# PMTF_Middle_board.net
KiCad netlist of a schematic drawn in Altium Designer
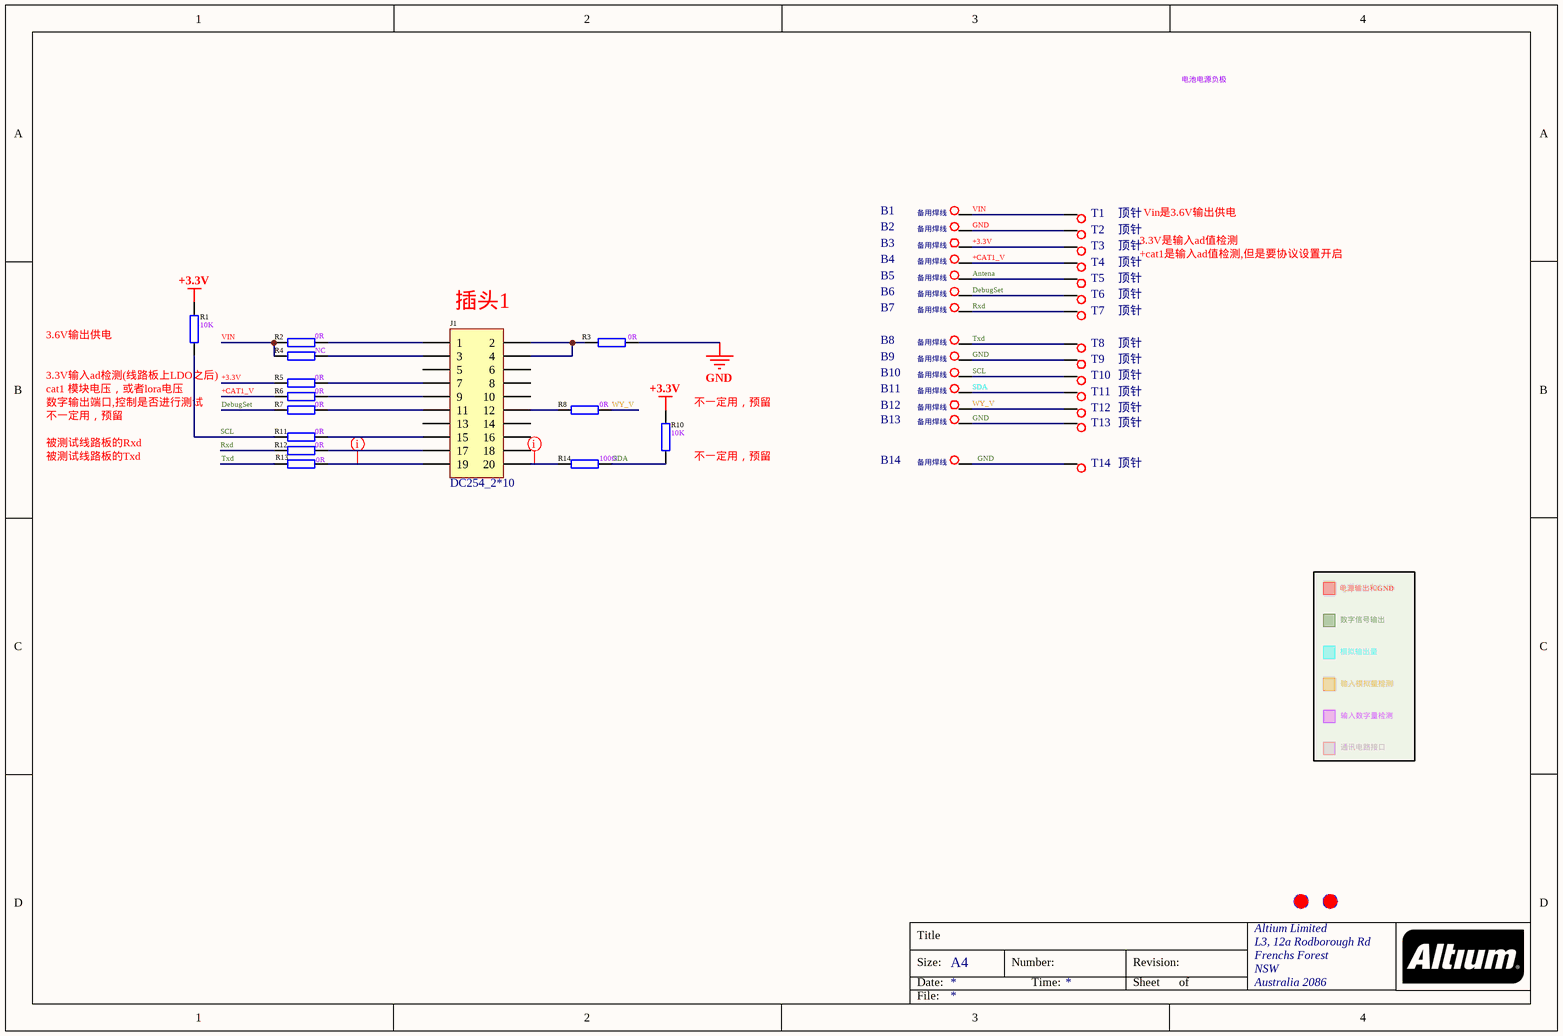
[diagram p0: PMTF_Middle_board.schdoc]

(export (version "E")
  (design (tool "Eeschema 10.0.6"))
  (components
    (comp (ref "B1")
      (value "备用焊线")
      (footprint "Connector:TestPoint")
      (description "通孔测试点")
      (fields (field (name "PART NUMBER") "AD_WXHJ_TEST-POINT_01"))
      (libsource (lib "Database_Libs2") (part "TEST-POINT"))
    )
    (comp (ref "B2")
      (value "备用焊线")
      (footprint "Connector:TestPoint")
      (description "通孔测试点")
      (fields (field (name "PART NUMBER") "AD_WXHJ_TEST-POINT_01"))
      (libsource (lib "Database_Libs2") (part "TEST-POINT"))
    )
    (comp (ref "B3")
      (value "备用焊线")
      (footprint "Connector:TestPoint")
      (description "通孔测试点")
      (fields (field (name "PART NUMBER") "AD_WXHJ_TEST-POINT_01"))
      (libsource (lib "Database_Libs2") (part "TEST-POINT"))
    )
    (comp (ref "B4")
      (value "备用焊线")
      (footprint "Connector:TestPoint")
      (description "通孔测试点")
      (fields (field (name "PART NUMBER") "AD_WXHJ_TEST-POINT_01"))
      (libsource (lib "Database_Libs2") (part "TEST-POINT"))
    )
    (comp (ref "B5")
      (value "备用焊线")
      (footprint "Connector:TestPoint")
      (description "通孔测试点")
      (fields (field (name "PART NUMBER") "AD_WXHJ_TEST-POINT_01"))
      (libsource (lib "Database_Libs2") (part "TEST-POINT"))
    )
    (comp (ref "B6")
      (value "备用焊线")
      (footprint "Connector:TestPoint")
      (description "通孔测试点")
      (fields (field (name "PART NUMBER") "AD_WXHJ_TEST-POINT_01"))
      (libsource (lib "Database_Libs2") (part "TEST-POINT"))
    )
    (comp (ref "B7")
      (value "备用焊线")
      (footprint "Connector:TestPoint")
      (description "通孔测试点")
      (fields (field (name "PART NUMBER") "AD_WXHJ_TEST-POINT_01"))
      (libsource (lib "Database_Libs2") (part "TEST-POINT"))
    )
    (comp (ref "B8")
      (value "备用焊线")
      (footprint "Connector:TestPoint")
      (description "通孔测试点")
      (fields (field (name "PART NUMBER") "AD_WXHJ_TEST-POINT_01"))
      (libsource (lib "Database_Libs2") (part "TEST-POINT"))
    )
    (comp (ref "B9")
      (value "备用焊线")
      (footprint "Connector:TestPoint")
      (description "通孔测试点")
      (fields (field (name "PART NUMBER") "AD_WXHJ_TEST-POINT_01"))
      (libsource (lib "Database_Libs2") (part "TEST-POINT"))
    )
    (comp (ref "B10")
      (value "备用焊线")
      (footprint "Connector:TestPoint")
      (description "通孔测试点")
      (fields (field (name "PART NUMBER") "AD_WXHJ_TEST-POINT_01"))
      (libsource (lib "Database_Libs2") (part "TEST-POINT"))
    )
    (comp (ref "B11")
      (value "备用焊线")
      (footprint "Connector:TestPoint")
      (description "通孔测试点")
      (fields (field (name "PART NUMBER") "AD_WXHJ_TEST-POINT_01"))
      (libsource (lib "Database_Libs2") (part "TEST-POINT"))
    )
    (comp (ref "B12")
      (value "备用焊线")
      (footprint "Connector:TestPoint")
      (description "通孔测试点")
      (fields (field (name "PART NUMBER") "AD_WXHJ_TEST-POINT_01"))
      (libsource (lib "Database_Libs2") (part "TEST-POINT"))
    )
    (comp (ref "B13")
      (value "备用焊线")
      (footprint "Connector:TestPoint")
      (description "通孔测试点")
      (fields (field (name "PART NUMBER") "AD_WXHJ_TEST-POINT_01"))
      (libsource (lib "Database_Libs2") (part "TEST-POINT"))
    )
    (comp (ref "B14")
      (value "备用焊线")
      (footprint "Connector:TestPoint")
      (description "通孔测试点")
      (fields (field (name "PART NUMBER") "AD_WXHJ_TEST-POINT_01"))
      (libsource (lib "Database_Libs2") (part "TEST-POINT"))
    )
    (comp (ref "J1")
      (value "DC254_2*10")
      (footprint "Connector:IDC2.54-LI-2x10P")
      (description "DC2 2.54mm 2x10pin,2.54mm间距，2x10pin，32×8.55×27.5mm,母头,双排,双排牛角座")
      (fields (field (name "PART NUMBER") "1010902-0139"))
      (libsource (lib "Database_Libs2") (part "DC254_2*10"))
    )
    (comp (ref "M1")
      (value "MARK")
      (footprint "Sign:MARK")
      (description "MARK点")
      (libsource (lib "XT-2312-Z1") (part "MARK"))
    )
    (comp (ref "M2")
      (value "MARK")
      (footprint "Sign:MARK")
      (description "MARK点")
      (libsource (lib "XT-2312-Z1") (part "MARK"))
    )
    (comp (ref "R1")
      (value "10K")
      (footprint "Resistor:R-1206")
      (description "0Ω,±5%,1/4W,1206,国巨,RC1206JR-070RL")
      (fields (field (name "PART NUMBER") "101010101-0013"))
      (libsource (lib "Database_Libs2") (part "RC06J_0R"))
    )
    (comp (ref "R2")
      (value "0R")
      (footprint "Resistor:R-1206")
      (description "0Ω,±5%,1/4W,1206,国巨,RC1206JR-070RL")
      (fields (field (name "PART NUMBER") "101010101-0013"))
      (libsource (lib "Database_Libs2") (part "RC06J_0R"))
    )
    (comp (ref "R3")
      (value "0R")
      (footprint "Resistor:R-1206")
      (description "0Ω,±5%,1/4W,1206,国巨,RC1206JR-070RL")
      (fields (field (name "PART NUMBER") "101010101-0013"))
      (libsource (lib "Database_Libs2") (part "RC06J_0R"))
    )
    (comp (ref "R4")
      (value "NC")
      (footprint "Resistor:R-1206")
      (description "0Ω,±5%,1/4W,1206,国巨,RC1206JR-070RL")
      (fields (field (name "PART NUMBER") "101010101-0013"))
      (libsource (lib "Database_Libs2") (part "RC06J_0R"))
    )
    (comp (ref "R5")
      (value "0R")
      (footprint "Resistor:R-1206")
      (description "0Ω,±5%,1/4W,1206,国巨,RC1206JR-070RL")
      (fields (field (name "PART NUMBER") "101010101-0013"))
      (libsource (lib "Database_Libs2") (part "RC06J_0R"))
    )
    (comp (ref "R6")
      (value "0R")
      (footprint "Resistor:R-1206")
      (description "0Ω,±5%,1/4W,1206,国巨,RC1206JR-070RL")
      (fields (field (name "PART NUMBER") "101010101-0013"))
      (libsource (lib "Database_Libs2") (part "RC06J_0R"))
    )
    (comp (ref "R7")
      (value "0R")
      (footprint "Resistor:R-1206")
      (description "0Ω,±5%,1/4W,1206,国巨,RC1206JR-070RL")
      (fields (field (name "PART NUMBER") "101010101-0013"))
      (libsource (lib "Database_Libs2") (part "RC06J_0R"))
    )
    (comp (ref "R8")
      (value "0R")
      (footprint "Resistor:R-1206")
      (description "0Ω,±5%,1/4W,1206,国巨,RC1206JR-070RL")
      (fields (field (name "PART NUMBER") "101010101-0013"))
      (libsource (lib "Database_Libs2") (part "RC06J_0R"))
    )
    (comp (ref "R10")
      (value "10K")
      (footprint "Resistor:R-1206")
      (description "0Ω,±5%,1/4W,1206,国巨,RC1206JR-070RL")
      (fields (field (name "PART NUMBER") "101010101-0013"))
      (libsource (lib "Database_Libs2") (part "RC06J_0R"))
    )
    (comp (ref "R11")
      (value "0R")
      (footprint "Resistor:R-1206")
      (description "0Ω,±5%,1/4W,1206,国巨,RC1206JR-070RL")
      (fields (field (name "PART NUMBER") "101010101-0013"))
      (libsource (lib "Database_Libs2") (part "RC06J_0R"))
    )
    (comp (ref "R12")
      (value "0R")
      (footprint "Resistor:R-1206")
      (description "0Ω,±5%,1/4W,1206,国巨,RC1206JR-070RL")
      (fields (field (name "PART NUMBER") "101010101-0013"))
      (libsource (lib "Database_Libs2") (part "RC06J_0R"))
    )
    (comp (ref "R13")
      (value "0R")
      (footprint "Resistor:R-1206")
      (description "0Ω,±5%,1/4W,1206,国巨,RC1206JR-070RL")
      (fields (field (name "PART NUMBER") "101010101-0013"))
      (libsource (lib "Database_Libs2") (part "RC06J_0R"))
    )
    (comp (ref "R14")
      (value "100Ω")
      (footprint "Resistor:R-1206")
      (description "0Ω,±5%,1/4W,1206,国巨,RC1206JR-070RL")
      (fields (field (name "PART NUMBER") "101010101-0013"))
      (libsource (lib "Database_Libs2") (part "RC06J_0R"))
    )
    (comp (ref "T1")
      (value "顶针")
      (footprint "Connector:TestPoint")
      (description "通孔测试点")
      (fields (field (name "PART NUMBER") "AD_WXHJ_TEST-POINT_01"))
      (libsource (lib "Database_Libs2") (part "TEST-POINT"))
    )
    (comp (ref "T2")
      (value "顶针")
      (footprint "Connector:TestPoint")
      (description "通孔测试点")
      (fields (field (name "PART NUMBER") "AD_WXHJ_TEST-POINT_01"))
      (libsource (lib "Database_Libs2") (part "TEST-POINT"))
    )
    (comp (ref "T3")
      (value "顶针")
      (footprint "Connector:TestPoint")
      (description "通孔测试点")
      (fields (field (name "PART NUMBER") "AD_WXHJ_TEST-POINT_01"))
      (libsource (lib "Database_Libs2") (part "TEST-POINT"))
    )
    (comp (ref "T4")
      (value "顶针")
      (footprint "Connector:TestPoint")
      (description "通孔测试点")
      (fields (field (name "PART NUMBER") "AD_WXHJ_TEST-POINT_01"))
      (libsource (lib "Database_Libs2") (part "TEST-POINT"))
    )
    (comp (ref "T5")
      (value "顶针")
      (footprint "Connector:TestPoint")
      (description "通孔测试点")
      (fields (field (name "PART NUMBER") "AD_WXHJ_TEST-POINT_01"))
      (libsource (lib "Database_Libs2") (part "TEST-POINT"))
    )
    (comp (ref "T6")
      (value "顶针")
      (footprint "Connector:TestPoint")
      (description "通孔测试点")
      (fields (field (name "PART NUMBER") "AD_WXHJ_TEST-POINT_01"))
      (libsource (lib "Database_Libs2") (part "TEST-POINT"))
    )
    (comp (ref "T7")
      (value "顶针")
      (footprint "Connector:TestPoint")
      (description "通孔测试点")
      (fields (field (name "PART NUMBER") "AD_WXHJ_TEST-POINT_01"))
      (libsource (lib "Database_Libs2") (part "TEST-POINT"))
    )
    (comp (ref "T8")
      (value "顶针")
      (footprint "Connector:TestPoint")
      (description "通孔测试点")
      (fields (field (name "PART NUMBER") "AD_WXHJ_TEST-POINT_01"))
      (libsource (lib "Database_Libs2") (part "TEST-POINT"))
    )
    (comp (ref "T9")
      (value "顶针")
      (footprint "Connector:TestPoint")
      (description "通孔测试点")
      (fields (field (name "PART NUMBER") "AD_WXHJ_TEST-POINT_01"))
      (libsource (lib "Database_Libs2") (part "TEST-POINT"))
    )
    (comp (ref "T10")
      (value "顶针")
      (footprint "Connector:TestPoint")
      (description "通孔测试点")
      (fields (field (name "PART NUMBER") "AD_WXHJ_TEST-POINT_01"))
      (libsource (lib "Database_Libs2") (part "TEST-POINT"))
    )
    (comp (ref "T11")
      (value "顶针")
      (footprint "Connector:TestPoint")
      (description "通孔测试点")
      (fields (field (name "PART NUMBER") "AD_WXHJ_TEST-POINT_01"))
      (libsource (lib "Database_Libs2") (part "TEST-POINT"))
    )
    (comp (ref "T12")
      (value "顶针")
      (footprint "Connector:TestPoint")
      (description "通孔测试点")
      (fields (field (name "PART NUMBER") "AD_WXHJ_TEST-POINT_01"))
      (libsource (lib "Database_Libs2") (part "TEST-POINT"))
    )
    (comp (ref "T13")
      (value "顶针")
      (footprint "Connector:TestPoint")
      (description "通孔测试点")
      (fields (field (name "PART NUMBER") "AD_WXHJ_TEST-POINT_01"))
      (libsource (lib "Database_Libs2") (part "TEST-POINT"))
    )
    (comp (ref "T14")
      (value "顶针")
      (footprint "Connector:TestPoint")
      (description "通孔测试点")
      (fields (field (name "PART NUMBER") "AD_WXHJ_TEST-POINT_01"))
      (libsource (lib "Database_Libs2") (part "TEST-POINT"))
    )
  )
  (nets
    (net (code "1") (name "+3.3V") (class "Default")
      (node (ref "B3") (pin "1") (pinfunction "1_1") (pintype "passive"))
      (node (ref "R1") (pin "1") (pinfunction "1_1") (pintype "passive"))
      (node (ref "R10") (pin "1") (pinfunction "1_1") (pintype "passive"))
      (node (ref "R5") (pin "1") (pinfunction "1_1") (pintype "passive"))
      (node (ref "T3") (pin "1") (pinfunction "1_1") (pintype "passive"))
    )
    (net (code "2") (name "/+CAT1_V") (class "Default")
      (node (ref "B4") (pin "1") (pinfunction "1_1") (pintype "passive"))
      (node (ref "R6") (pin "1") (pinfunction "1_1") (pintype "passive"))
      (node (ref "T4") (pin "1") (pinfunction "1_1") (pintype "passive"))
    )
    (net (code "3") (name "/Antena") (class "Default")
      (node (ref "B5") (pin "1") (pinfunction "1_1") (pintype "passive"))
      (node (ref "T5") (pin "1") (pinfunction "1_1") (pintype "passive"))
    )
    (net (code "4") (name "/DebugSet") (class "Default")
      (node (ref "B6") (pin "1") (pinfunction "1_1") (pintype "passive"))
      (node (ref "R7") (pin "1") (pinfunction "1_1") (pintype "passive"))
      (node (ref "T6") (pin "1") (pinfunction "1_1") (pintype "passive"))
    )
    (net (code "5") (name "/Rxd") (class "Default")
      (node (ref "B7") (pin "1") (pinfunction "1_1") (pintype "passive"))
      (node (ref "R12") (pin "1") (pinfunction "1_1") (pintype "passive"))
      (node (ref "T7") (pin "1") (pinfunction "1_1") (pintype "passive"))
    )
    (net (code "6") (name "/SCL") (class "Default")
      (node (ref "B10") (pin "1") (pinfunction "1_1") (pintype "passive"))
      (node (ref "R1") (pin "2") (pinfunction "2_2") (pintype "passive"))
      (node (ref "R11") (pin "1") (pinfunction "1_1") (pintype "passive"))
      (node (ref "T10") (pin "1") (pinfunction "1_1") (pintype "passive"))
    )
    (net (code "7") (name "/SDA") (class "Default")
      (node (ref "B11") (pin "1") (pinfunction "1_1") (pintype "passive"))
      (node (ref "R10") (pin "2") (pinfunction "2_2") (pintype "passive"))
      (node (ref "R14") (pin "1") (pinfunction "1_1") (pintype "passive"))
      (node (ref "T11") (pin "1") (pinfunction "1_1") (pintype "passive"))
    )
    (net (code "8") (name "/Txd") (class "Default")
      (node (ref "B8") (pin "1") (pinfunction "1_1") (pintype "passive"))
      (node (ref "R13") (pin "1") (pinfunction "1_1") (pintype "passive"))
      (node (ref "T8") (pin "1") (pinfunction "1_1") (pintype "passive"))
    )
    (net (code "9") (name "/VIN") (class "Default")
      (node (ref "B1") (pin "1") (pinfunction "1_1") (pintype "passive"))
      (node (ref "R2") (pin "1") (pinfunction "1_1") (pintype "passive"))
      (node (ref "R4") (pin "1") (pinfunction "1_1") (pintype "passive"))
      (node (ref "T1") (pin "1") (pinfunction "1_1") (pintype "passive"))
    )
    (net (code "10") (name "/WY_V") (class "Default")
      (node (ref "B12") (pin "1") (pinfunction "1_1") (pintype "passive"))
      (node (ref "R8") (pin "1") (pinfunction "1_1") (pintype "passive"))
      (node (ref "T12") (pin "1") (pinfunction "1_1") (pintype "passive"))
    )
    (net (code "11") (name "GND") (class "Default")
      (node (ref "B13") (pin "1") (pinfunction "1_1") (pintype "passive"))
      (node (ref "B14") (pin "1") (pinfunction "1_1") (pintype "passive"))
      (node (ref "B2") (pin "1") (pinfunction "1_1") (pintype "passive"))
      (node (ref "B9") (pin "1") (pinfunction "1_1") (pintype "passive"))
      (node (ref "R3") (pin "1") (pinfunction "1_1") (pintype "passive"))
      (node (ref "T13") (pin "1") (pinfunction "1_1") (pintype "passive"))
      (node (ref "T14") (pin "1") (pinfunction "1_1") (pintype "passive"))
      (node (ref "T2") (pin "1") (pinfunction "1_1") (pintype "passive"))
      (node (ref "T9") (pin "1") (pinfunction "1_1") (pintype "passive"))
    )
    (net (code "12") (name "Net-(J1-Pad1)") (class "Default")
      (node (ref "J1") (pin "1") (pinfunction "1_1") (pintype "passive"))
      (node (ref "R2") (pin "2") (pinfunction "2_2") (pintype "passive"))
    )
    (net (code "13") (name "Net-(J1-Pad2)") (class "Default")
      (node (ref "J1") (pin "2") (pinfunction "2_2") (pintype "passive"))
      (node (ref "J1") (pin "4") (pinfunction "4_4") (pintype "passive"))
      (node (ref "R3") (pin "2") (pinfunction "2_2") (pintype "passive"))
    )
    (net (code "14") (name "Net-(J1-Pad3)") (class "Default")
      (node (ref "J1") (pin "3") (pinfunction "3_3") (pintype "passive"))
      (node (ref "R4") (pin "2") (pinfunction "2_2") (pintype "passive"))
    )
    (net (code "15") (name "Net-(J1-Pad7)") (class "Default")
      (node (ref "J1") (pin "7") (pinfunction "7_7") (pintype "passive"))
      (node (ref "R5") (pin "2") (pinfunction "2_2") (pintype "passive"))
    )
    (net (code "16") (name "Net-(J1-Pad9)") (class "Default")
      (node (ref "J1") (pin "9") (pinfunction "9_9") (pintype "passive"))
      (node (ref "R6") (pin "2") (pinfunction "2_2") (pintype "passive"))
    )
    (net (code "17") (name "Net-(J1-Pad11)") (class "Default")
      (node (ref "J1") (pin "11") (pinfunction "11_11") (pintype "passive"))
      (node (ref "R7") (pin "2") (pinfunction "2_2") (pintype "passive"))
    )
    (net (code "18") (name "Net-(J1-Pad12)") (class "Default")
      (node (ref "J1") (pin "12") (pinfunction "12_12") (pintype "passive"))
      (node (ref "R8") (pin "2") (pinfunction "2_2") (pintype "passive"))
    )
    (net (code "19") (name "Net-(J1-Pad15)") (class "Default")
      (node (ref "J1") (pin "15") (pinfunction "15_15") (pintype "passive"))
      (node (ref "R11") (pin "2") (pinfunction "2_2") (pintype "passive"))
    )
    (net (code "20") (name "Net-(J1-Pad17)") (class "Default")
      (node (ref "J1") (pin "17") (pinfunction "17_17") (pintype "passive"))
      (node (ref "R12") (pin "2") (pinfunction "2_2") (pintype "passive"))
    )
    (net (code "21") (name "Net-(J1-Pad19)") (class "Default")
      (node (ref "J1") (pin "19") (pinfunction "19_19") (pintype "passive"))
      (node (ref "R13") (pin "2") (pinfunction "2_2") (pintype "passive"))
    )
    (net (code "22") (name "Net-(J1-Pad20)") (class "Default")
      (node (ref "J1") (pin "20") (pinfunction "20_20") (pintype "passive"))
      (node (ref "R14") (pin "2") (pinfunction "2_2") (pintype "passive"))
    )
    (net (code "23") (name "unconnected-(J1-Pad5)") (class "Default")
      (node (ref "J1") (pin "5") (pinfunction "5_5") (pintype "passive"))
    )
    (net (code "24") (name "unconnected-(J1-Pad6)") (class "Default")
      (node (ref "J1") (pin "6") (pinfunction "6_6") (pintype "passive"))
    )
    (net (code "25") (name "unconnected-(J1-Pad8)") (class "Default")
      (node (ref "J1") (pin "8") (pinfunction "8_8") (pintype "passive"))
    )
    (net (code "26") (name "unconnected-(J1-Pad10)") (class "Default")
      (node (ref "J1") (pin "10") (pinfunction "10_10") (pintype "passive"))
    )
    (net (code "27") (name "unconnected-(J1-Pad13)") (class "Default")
      (node (ref "J1") (pin "13") (pinfunction "13_13") (pintype "passive"))
    )
    (net (code "28") (name "unconnected-(J1-Pad14)") (class "Default")
      (node (ref "J1") (pin "14") (pinfunction "14_14") (pintype "passive"))
    )
    (net (code "29") (name "unconnected-(J1-Pad16)") (class "Default")
      (node (ref "J1") (pin "16") (pinfunction "16_16") (pintype "passive"))
    )
    (net (code "30") (name "unconnected-(J1-Pad18)") (class "Default")
      (node (ref "J1") (pin "18") (pinfunction "18_18") (pintype "passive"))
    )
  )
)
